# four_axis_part3.net
KiCad netlist of a schematic drawn in Altium Designer
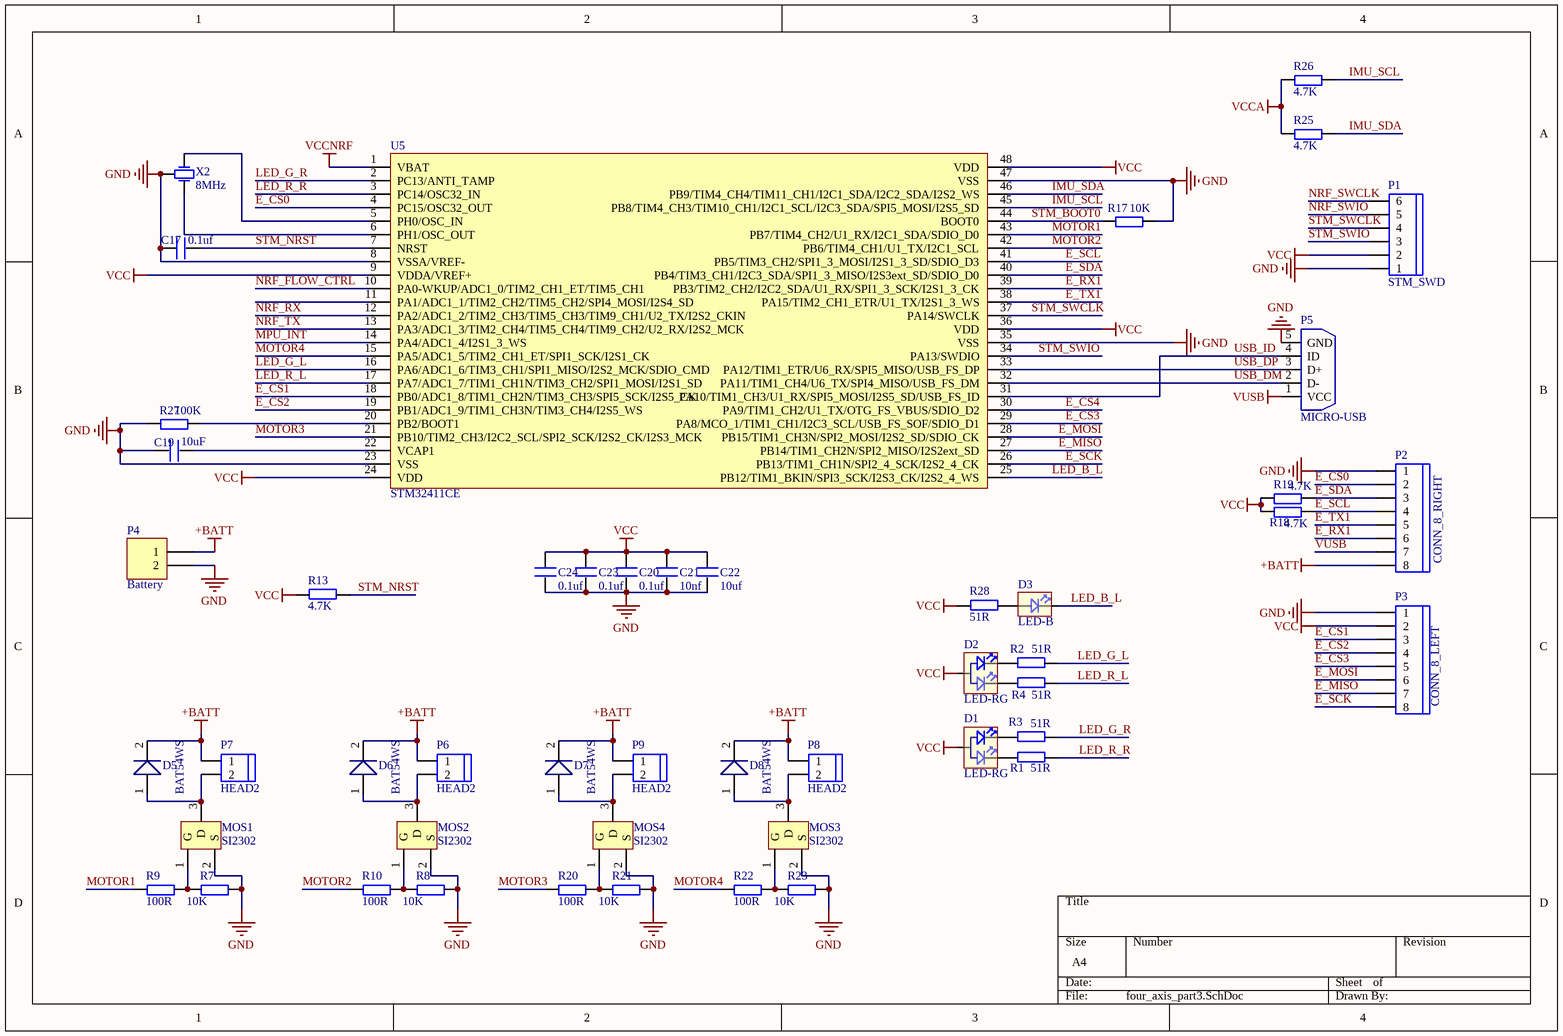
[diagram p0: four_axis_part3.SchDoc]

(export (version "E")
  (design (tool "Eeschema 10.0.6"))
  (components
    (comp (ref "C17") (value "0.1uf") (footprint "0603P") (libsource (lib "MiniFly ") (part "C")))
    (comp (ref "C19") (value "10uF") (footprint "0603P") (libsource (lib "MiniFly ") (part "C")))
    (comp (ref "C20") (value "0.1uf") (footprint "0603P") (libsource (lib "MiniFly ") (part "C")))
    (comp (ref "C21") (value "10nf") (footprint "0603P") (libsource (lib "MiniFly ") (part "C")))
    (comp (ref "C22") (value "10uf") (footprint "0603P") (libsource (lib "MiniFly ") (part "C")))
    (comp (ref "C23") (value "0.1uf") (footprint "0603P") (libsource (lib "MiniFly ") (part "C")))
    (comp (ref "C24") (value "0.1uf") (footprint "0603P") (libsource (lib "MiniFly ") (part "C")))
    (comp (ref "D1")
      (value "LED-RG")
      (footprint "LED1206  侧贴")
      (description "LED 1206 侧贴 双色")
      (libsource (lib "MiniFly ") (part "LED 1206 侧贴 双色"))
    )
    (comp (ref "D2")
      (value "LED-RG")
      (footprint "LED1206  侧贴")
      (description "LED 1206 侧贴 双色")
      (libsource (lib "MiniFly ") (part "LED 1206 侧贴 双色"))
    )
    (comp (ref "D3")
      (value "LED-B")
      (footprint "LED1206  侧贴")
      (description "LED 1206 侧贴  单色")
      (libsource (lib "MiniFly ") (part "LED 1206 侧贴  单色"))
    )
    (comp (ref "D5")
      (value "BAT54WS")
      (footprint "SOD-323")
      (description "单肖特基二极管")
      (libsource (lib "MiniFly ") (part "BAT54"))
    )
    (comp (ref "D6")
      (value "BAT54WS")
      (footprint "SOD-323")
      (description "单肖特基二极管")
      (libsource (lib "MiniFly ") (part "BAT54"))
    )
    (comp (ref "D7")
      (value "BAT54WS")
      (footprint "SOD-323")
      (description "单肖特基二极管")
      (libsource (lib "MiniFly ") (part "BAT54"))
    )
    (comp (ref "D8")
      (value "BAT54WS")
      (footprint "SOD-323")
      (description "单肖特基二极管")
      (libsource (lib "MiniFly ") (part "BAT54"))
    )
    (comp (ref "MOS1")
      (value "SI2302")
      (footprint "SO-G3/C2.5")
      (description "AP2306")
      (libsource (lib "MiniFly ") (part "MOS-N"))
    )
    (comp (ref "MOS2")
      (value "SI2302")
      (footprint "SO-G3/C2.5")
      (description "AP2306")
      (libsource (lib "MiniFly ") (part "MOS-N"))
    )
    (comp (ref "MOS3")
      (value "SI2302")
      (footprint "SO-G3/C2.5")
      (description "AP2306")
      (libsource (lib "MiniFly ") (part "MOS-N"))
    )
    (comp (ref "MOS4")
      (value "SI2302")
      (footprint "SO-G3/C2.5")
      (description "AP2306")
      (libsource (lib "MiniFly ") (part "MOS-N"))
    )
    (comp (ref "P1") (value "STM_SWD") (footprint "SH1.0-6P") (libsource (lib "MiniFly ") (part "HEAD6")))
    (comp (ref "P2")
      (value "CONN_8_RIGHT")
      (footprint "HEADER8-2.0MM")
      (libsource (lib "MiniFly ") (part "HEAD8"))
    )
    (comp (ref "P3")
      (value "CONN_8_LEFT")
      (footprint "HEADER8-2.0MM")
      (libsource (lib "MiniFly ") (part "HEAD8"))
    )
    (comp (ref "P4")
      (value "Battery")
      (footprint "HDR1X2")
      (description "Header, 2-Pin")
      (fields (field (name "PUBLISHER") "Altium Limited"))
      (libsource (lib "MiniFly ") (part "Header 2"))
    )
    (comp (ref "P5")
      (value "MICRO-USB")
      (footprint "MICRO_USB5P_SOP")
      (libsource (lib "MiniFly ") (part "USB5"))
    )
    (comp (ref "P6") (value "HEAD2") (footprint "HEADER2-1.25MM") (libsource (lib "MiniFly ") (part "HEAD2")))
    (comp (ref "P7") (value "HEAD2") (footprint "HEADER2-1.25MM") (libsource (lib "MiniFly ") (part "HEAD2")))
    (comp (ref "P8") (value "HEAD2") (footprint "HEADER2-1.25MM") (libsource (lib "MiniFly ") (part "HEAD2")))
    (comp (ref "P9") (value "HEAD2") (footprint "HEADER2-1.25MM") (libsource (lib "MiniFly ") (part "HEAD2")))
    (comp (ref "R1") (value "51R") (footprint "0402") (libsource (lib "MiniFly ") (part "R")))
    (comp (ref "R2") (value "51R") (footprint "0402") (libsource (lib "MiniFly ") (part "R")))
    (comp (ref "R3") (value "51R") (footprint "0402") (libsource (lib "MiniFly ") (part "R")))
    (comp (ref "R4") (value "51R") (footprint "0402") (libsource (lib "MiniFly ") (part "R")))
    (comp (ref "R7") (value "10K") (footprint "0402") (libsource (lib "MiniFly ") (part "R")))
    (comp (ref "R8") (value "10K") (footprint "0402") (libsource (lib "MiniFly ") (part "R")))
    (comp (ref "R9") (value "100R") (footprint "0402") (libsource (lib "MiniFly ") (part "R")))
    (comp (ref "R10") (value "100R") (footprint "0402") (libsource (lib "MiniFly ") (part "R")))
    (comp (ref "R13") (value "4.7K") (footprint "0402") (libsource (lib "MiniFly ") (part "R")))
    (comp (ref "R17") (value "10K") (footprint "0402") (libsource (lib "MiniFly ") (part "R")))
    (comp (ref "R18") (value "4.7K") (footprint "0402") (libsource (lib "MiniFly ") (part "R")))
    (comp (ref "R19") (value "4.7K") (footprint "0402") (libsource (lib "MiniFly ") (part "R")))
    (comp (ref "R20") (value "100R") (footprint "0402") (libsource (lib "MiniFly ") (part "R")))
    (comp (ref "R21") (value "10K") (footprint "0402") (libsource (lib "MiniFly ") (part "R")))
    (comp (ref "R22") (value "100R") (footprint "0402") (libsource (lib "MiniFly ") (part "R")))
    (comp (ref "R23") (value "10K") (footprint "0402") (libsource (lib "MiniFly ") (part "R")))
    (comp (ref "R25") (value "4.7K") (footprint "0402") (libsource (lib "MiniFly ") (part "R")))
    (comp (ref "R26") (value "4.7K") (footprint "0402") (libsource (lib "MiniFly ") (part "R")))
    (comp (ref "R27") (value "100K") (footprint "0402") (libsource (lib "MiniFly ") (part "R")))
    (comp (ref "R28") (value "51R") (footprint "0402") (libsource (lib "MiniFly ") (part "R")))
    (comp (ref "U5")
      (value "STM32411CE")
      (footprint "UFQFPN48")
      (description "STM32411xC_xE")
      (libsource (lib "MiniFly ") (part "STM32F411xC_xE"))
    )
    (comp (ref "X2") (value "8MHz") (footprint "XTAL3215") (libsource (lib "MiniFly ") (part "XTAL-3215")))
  )
  (nets
    (net (code "1") (name "+BATT") (class "Default")
      (node (ref "D5") (pin "2") (pinfunction "2_2") (pintype "passive"))
      (node (ref "D6") (pin "2") (pinfunction "2_2") (pintype "passive"))
      (node (ref "D7") (pin "2") (pinfunction "2_2") (pintype "passive"))
      (node (ref "D8") (pin "2") (pinfunction "2_2") (pintype "passive"))
      (node (ref "P2") (pin "8") (pinfunction "8_8") (pintype "passive"))
      (node (ref "P4") (pin "1") (pinfunction "1_1") (pintype "passive"))
      (node (ref "P6") (pin "1") (pinfunction "1_1") (pintype "passive"))
      (node (ref "P7") (pin "1") (pinfunction "1_1") (pintype "passive"))
      (node (ref "P8") (pin "1") (pinfunction "1_1") (pintype "passive"))
      (node (ref "P9") (pin "1") (pinfunction "1_1") (pintype "passive"))
    )
    (net (code "2") (name "/E_CS0") (class "Default")
      (node (ref "P2") (pin "2") (pinfunction "2_2") (pintype "passive"))
      (node (ref "U5") (pin "4") (pinfunction "PC15/OSC32_OUT_4") (pintype "passive"))
    )
    (net (code "3") (name "/E_CS1") (class "Default")
      (node (ref "P3") (pin "3") (pinfunction "3_3") (pintype "passive"))
      (node (ref "U5") (pin "18") (pinfunction "PB0/ADC1_8/TIM1_CH2N/TIM3_CH3/SPI5_SCK/I2S5_CK_18") (pintype "passive"))
    )
    (net (code "4") (name "/E_CS2") (class "Default")
      (node (ref "P3") (pin "4") (pinfunction "4_4") (pintype "passive"))
      (node (ref "U5") (pin "19") (pinfunction "PB1/ADC1_9/TIM1_CH3N/TIM3_CH4/I2S5_WS_19") (pintype "passive"))
    )
    (net (code "5") (name "/E_CS3") (class "Default")
      (node (ref "P3") (pin "5") (pinfunction "5_5") (pintype "passive"))
      (node (ref "U5") (pin "29") (pinfunction "PA8/MCO_1/TIM1_CH1/I2C3_SCL/USB_FS_SOF/SDIO_D1_29") (pintype "passive"))
    )
    (net (code "6") (name "/E_CS4") (class "Default")
      (node (ref "U5") (pin "30") (pinfunction "PA9/TIM1_CH2/U1_TX/OTG_FS_VBUS/SDIO_D2_30") (pintype "passive"))
    )
    (net (code "7") (name "/E_MISO") (class "Default")
      (node (ref "P3") (pin "7") (pinfunction "7_7") (pintype "passive"))
      (node (ref "U5") (pin "27") (pinfunction "PB14/TIM1_CH2N/SPI2_MISO/I2S2ext_SD_27") (pintype "passive"))
    )
    (net (code "8") (name "/E_MOSI") (class "Default")
      (node (ref "P3") (pin "6") (pinfunction "6_6") (pintype "passive"))
      (node (ref "U5") (pin "28") (pinfunction "PB15/TIM1_CH3N/SPI2_MOSI/I2S2_SD/SDIO_CK_28") (pintype "passive"))
    )
    (net (code "9") (name "/E_RX1") (class "Default")
      (node (ref "P2") (pin "6") (pinfunction "6_6") (pintype "passive"))
      (node (ref "U5") (pin "39") (pinfunction "PB3/TIM2_CH2/I2C2_SDA/U1_RX/SPI1_3_SCK/I2S1_3_CK_39") (pintype "passive"))
    )
    (net (code "10") (name "/E_SCK") (class "Default")
      (node (ref "P3") (pin "8") (pinfunction "8_8") (pintype "passive"))
      (node (ref "U5") (pin "26") (pinfunction "PB13/TIM1_CH1N/SPI2_4_SCK/I2S2_4_CK_26") (pintype "passive"))
    )
    (net (code "11") (name "/E_SCL") (class "Default")
      (node (ref "P2") (pin "4") (pinfunction "4_4") (pintype "passive"))
      (node (ref "R18") (pin "2") (pintype "passive"))
      (node (ref "U5") (pin "41") (pinfunction "PB5/TIM3_CH2/SPI1_3_MOSI/I2S1_3_SD/SDIO_D3_41") (pintype "passive"))
    )
    (net (code "12") (name "/E_SDA") (class "Default")
      (node (ref "P2") (pin "3") (pinfunction "3_3") (pintype "passive"))
      (node (ref "R19") (pin "2") (pintype "passive"))
      (node (ref "U5") (pin "40") (pinfunction "PB4/TIM3_CH1/I2C3_SDA/SPI1_3_MISO/I2S3ext_SD/SDIO_D0_40") (pintype "passive"))
    )
    (net (code "13") (name "/E_TX1") (class "Default")
      (node (ref "P2") (pin "5") (pinfunction "5_5") (pintype "passive"))
      (node (ref "U5") (pin "38") (pinfunction "PA15/TIM2_CH1_ETR/U1_TX/I2S1_3_WS_38") (pintype "passive"))
    )
    (net (code "14") (name "/IMU_SCL") (class "Default")
      (node (ref "R26") (pin "2") (pintype "passive"))
      (node (ref "U5") (pin "45") (pinfunction "PB8/TIM4_CH3/TIM10_CH1/I2C1_SCL/I2C3_SDA/SPI5_MOSI/I2S5_SD_45") (pintype "passive"))
    )
    (net (code "15") (name "/IMU_SDA") (class "Default")
      (node (ref "R25") (pin "2") (pintype "passive"))
      (node (ref "U5") (pin "46") (pinfunction "PB9/TIM4_CH4/TIM11_CH1/I2C1_SDA/I2C2_SDA/I2S2_WS_46") (pintype "passive"))
    )
    (net (code "16") (name "/LED_B_L") (class "Default")
      (node (ref "D3") (pin "1") (pinfunction "1_1") (pintype "passive"))
      (node (ref "U5") (pin "25") (pinfunction "PB12/TIM1_BKIN/SPI3_SCK/I2S3_CK/I2S2_4_WS_25") (pintype "passive"))
    )
    (net (code "17") (name "/LED_G_L") (class "Default")
      (node (ref "R2") (pin "1") (pintype "passive"))
      (node (ref "U5") (pin "16") (pinfunction "PA6/ADC1_6/TIM3_CH1/SPI1_MISO/I2S2_MCK/SDIO_CMD_16") (pintype "passive"))
    )
    (net (code "18") (name "/LED_G_R") (class "Default")
      (node (ref "R3") (pin "1") (pintype "passive"))
      (node (ref "U5") (pin "2") (pinfunction "PC13/ANTI_TAMP_2") (pintype "passive"))
    )
    (net (code "19") (name "/LED_R_L") (class "Default")
      (node (ref "R4") (pin "1") (pintype "passive"))
      (node (ref "U5") (pin "17") (pinfunction "PA7/ADC1_7/TIM1_CH1N/TIM3_CH2/SPI1_MOSI/I2S1_SD_17") (pintype "passive"))
    )
    (net (code "20") (name "/LED_R_R") (class "Default")
      (node (ref "R1") (pin "1") (pintype "passive"))
      (node (ref "U5") (pin "3") (pinfunction "PC14/OSC32_IN_3") (pintype "passive"))
    )
    (net (code "21") (name "/MOTOR1") (class "Default")
      (node (ref "R9") (pin "1") (pintype "passive"))
      (node (ref "U5") (pin "43") (pinfunction "PB7/TIM4_CH2/U1_RX/I2C1_SDA/SDIO_D0_43") (pintype "passive"))
    )
    (net (code "22") (name "/MOTOR2") (class "Default")
      (node (ref "R10") (pin "1") (pintype "passive"))
      (node (ref "U5") (pin "42") (pinfunction "PB6/TIM4_CH1/U1_TX/I2C1_SCL_42") (pintype "passive"))
    )
    (net (code "23") (name "/MOTOR3") (class "Default")
      (node (ref "R20") (pin "1") (pintype "passive"))
      (node (ref "U5") (pin "21") (pinfunction "PB10/TIM2_CH3/I2C2_SCL/SPI2_SCK/I2S2_CK/I2S3_MCK_21") (pintype "passive"))
    )
    (net (code "24") (name "/MOTOR4") (class "Default")
      (node (ref "R22") (pin "1") (pintype "passive"))
      (node (ref "U5") (pin "15") (pinfunction "PA5/ADC1_5/TIM2_CH1_ET/SPI1_SCK/I2S1_CK_15") (pintype "passive"))
    )
    (net (code "25") (name "/MPU_INT") (class "Default")
      (node (ref "U5") (pin "14") (pinfunction "PA4/ADC1_4/I2S1_3_WS_14") (pintype "passive"))
    )
    (net (code "26") (name "/NRF_FLOW_CTRL") (class "Default")
      (node (ref "U5") (pin "10") (pinfunction "PA0-WKUP/ADC1_0/TIM2_CH1_ET/TIM5_CH1_10") (pintype "passive"))
    )
    (net (code "27") (name "/NRF_RX") (class "Default")
      (node (ref "U5") (pin "12") (pinfunction "PA2/ADC1_2/TIM2_CH3/TIM5_CH3/TIM9_CH1/U2_TX/I2S2_CKIN_12") (pintype "passive"))
    )
    (net (code "28") (name "/NRF_SWCLK") (class "Default")
      (node (ref "P1") (pin "6") (pinfunction "6_6") (pintype "passive"))
    )
    (net (code "29") (name "/NRF_SWIO") (class "Default")
      (node (ref "P1") (pin "5") (pinfunction "5_5") (pintype "passive"))
    )
    (net (code "30") (name "/NRF_TX") (class "Default")
      (node (ref "U5") (pin "13") (pinfunction "PA3/ADC1_3/TIM2_CH4/TIM5_CH4/TIM9_CH2/U2_RX/I2S2_MCK_13") (pintype "passive"))
    )
    (net (code "31") (name "/STM_BOOT0") (class "Default")
      (node (ref "R17") (pin "1") (pintype "passive"))
      (node (ref "U5") (pin "44") (pinfunction "BOOT0_44") (pintype "passive"))
    )
    (net (code "32") (name "/STM_NRST") (class "Default")
      (node (ref "C17") (pin "2") (pintype "passive"))
      (node (ref "R13") (pin "1") (pintype "passive"))
      (node (ref "U5") (pin "7") (pinfunction "NRST_7") (pintype "passive"))
    )
    (net (code "33") (name "/STM_SWCLK") (class "Default")
      (node (ref "P1") (pin "4") (pinfunction "4_4") (pintype "passive"))
      (node (ref "U5") (pin "37") (pinfunction "PA14/SWCLK_37") (pintype "passive"))
    )
    (net (code "34") (name "/STM_SWIO") (class "Default")
      (node (ref "P1") (pin "3") (pinfunction "3_3") (pintype "passive"))
      (node (ref "U5") (pin "34") (pinfunction "PA13/SWDIO_34") (pintype "passive"))
    )
    (net (code "35") (name "/USB_DM") (class "Default")
      (node (ref "P5") (pin "2") (pinfunction "D-_2") (pintype "passive"))
      (node (ref "U5") (pin "32") (pinfunction "PA11/TIM1_CH4/U6_TX/SPI4_MISO/USB_FS_DM_32") (pintype "passive"))
    )
    (net (code "36") (name "/USB_DP") (class "Default")
      (node (ref "P5") (pin "3") (pinfunction "D+_3") (pintype "passive"))
      (node (ref "U5") (pin "33") (pinfunction "PA12/TIM1_ETR/U6_RX/SPI5_MISO/USB_FS_DP_33") (pintype "passive"))
    )
    (net (code "37") (name "/USB_ID") (class "Default")
      (node (ref "P5") (pin "4") (pinfunction "ID_4") (pintype "passive"))
      (node (ref "U5") (pin "31") (pinfunction "PA10/TIM1_CH3/U1_RX/SPI5_MOSI/I2S5_SD/USB_FS_ID_31") (pintype "passive"))
    )
    (net (code "38") (name "GND") (class "Default")
      (node (ref "C17") (pin "1") (pintype "passive"))
      (node (ref "C19") (pin "1") (pintype "passive"))
      (node (ref "C20") (pin "1") (pintype "passive"))
      (node (ref "C21") (pin "1") (pintype "passive"))
      (node (ref "C22") (pin "1") (pintype "passive"))
      (node (ref "C23") (pin "1") (pintype "passive"))
      (node (ref "C24") (pin "1") (pintype "passive"))
      (node (ref "MOS1") (pin "2") (pinfunction "S_2") (pintype "passive"))
      (node (ref "MOS2") (pin "2") (pinfunction "S_2") (pintype "passive"))
      (node (ref "MOS3") (pin "2") (pinfunction "S_2") (pintype "passive"))
      (node (ref "MOS4") (pin "2") (pinfunction "S_2") (pintype "passive"))
      (node (ref "P1") (pin "1") (pinfunction "1_1") (pintype "passive"))
      (node (ref "P2") (pin "1") (pinfunction "1_1") (pintype "passive"))
      (node (ref "P3") (pin "1") (pinfunction "1_1") (pintype "passive"))
      (node (ref "P4") (pin "2") (pinfunction "2_2") (pintype "passive"))
      (node (ref "P5") (pin "5") (pinfunction "GND_5") (pintype "passive"))
      (node (ref "R17") (pin "2") (pintype "passive"))
      (node (ref "R21") (pin "2") (pintype "passive"))
      (node (ref "R23") (pin "2") (pintype "passive"))
      (node (ref "R27") (pin "1") (pintype "passive"))
      (node (ref "R7") (pin "2") (pintype "passive"))
      (node (ref "R8") (pin "2") (pintype "passive"))
      (node (ref "U5") (pin "23") (pinfunction "VSS_23") (pintype "passive"))
      (node (ref "U5") (pin "35") (pinfunction "VSS_35") (pintype "passive"))
      (node (ref "U5") (pin "47") (pinfunction "VSS_47") (pintype "passive"))
      (node (ref "U5") (pin "8") (pinfunction "VSSA/VREF-_8") (pintype "passive"))
      (node (ref "X2") (pin "2") (pinfunction "GND_2") (pintype "passive"))
    )
    (net (code "39") (name "Net-(D1-Pad1)") (class "Default")
      (node (ref "D1") (pin "1") (pinfunction "1_1") (pintype "passive"))
      (node (ref "R1") (pin "2") (pintype "passive"))
    )
    (net (code "40") (name "Net-(D1-Pad2)") (class "Default")
      (node (ref "D1") (pin "2") (pinfunction "2_2") (pintype "passive"))
      (node (ref "R3") (pin "2") (pintype "passive"))
    )
    (net (code "41") (name "Net-(D2-Pad1)") (class "Default")
      (node (ref "D2") (pin "1") (pinfunction "1_1") (pintype "passive"))
      (node (ref "R4") (pin "2") (pintype "passive"))
    )
    (net (code "42") (name "Net-(D2-Pad2)") (class "Default")
      (node (ref "D2") (pin "2") (pinfunction "2_2") (pintype "passive"))
      (node (ref "R2") (pin "2") (pintype "passive"))
    )
    (net (code "43") (name "Net-(D3-Pad3)") (class "Default")
      (node (ref "D3") (pin "3") (pinfunction "3_3") (pintype "passive"))
      (node (ref "R28") (pin "1") (pintype "passive"))
    )
    (net (code "44") (name "Net-(MOS1-D)") (class "Default")
      (node (ref "D5") (pin "1") (pinfunction "1_1") (pintype "passive"))
      (node (ref "MOS1") (pin "3") (pinfunction "D_3") (pintype "passive"))
      (node (ref "P7") (pin "2") (pinfunction "2_2") (pintype "passive"))
    )
    (net (code "45") (name "Net-(MOS1-G)") (class "Default")
      (node (ref "MOS1") (pin "1") (pinfunction "G_1") (pintype "passive"))
      (node (ref "R7") (pin "1") (pintype "passive"))
      (node (ref "R9") (pin "2") (pintype "passive"))
    )
    (net (code "46") (name "Net-(MOS2-D)") (class "Default")
      (node (ref "D6") (pin "1") (pinfunction "1_1") (pintype "passive"))
      (node (ref "MOS2") (pin "3") (pinfunction "D_3") (pintype "passive"))
      (node (ref "P6") (pin "2") (pinfunction "2_2") (pintype "passive"))
    )
    (net (code "47") (name "Net-(MOS2-G)") (class "Default")
      (node (ref "MOS2") (pin "1") (pinfunction "G_1") (pintype "passive"))
      (node (ref "R10") (pin "2") (pintype "passive"))
      (node (ref "R8") (pin "1") (pintype "passive"))
    )
    (net (code "48") (name "Net-(MOS3-D)") (class "Default")
      (node (ref "D8") (pin "1") (pinfunction "1_1") (pintype "passive"))
      (node (ref "MOS3") (pin "3") (pinfunction "D_3") (pintype "passive"))
      (node (ref "P8") (pin "2") (pinfunction "2_2") (pintype "passive"))
    )
    (net (code "49") (name "Net-(MOS3-G)") (class "Default")
      (node (ref "MOS3") (pin "1") (pinfunction "G_1") (pintype "passive"))
      (node (ref "R22") (pin "2") (pintype "passive"))
      (node (ref "R23") (pin "1") (pintype "passive"))
    )
    (net (code "50") (name "Net-(MOS4-D)") (class "Default")
      (node (ref "D7") (pin "1") (pinfunction "1_1") (pintype "passive"))
      (node (ref "MOS4") (pin "3") (pinfunction "D_3") (pintype "passive"))
      (node (ref "P9") (pin "2") (pinfunction "2_2") (pintype "passive"))
    )
    (net (code "51") (name "Net-(MOS4-G)") (class "Default")
      (node (ref "MOS4") (pin "1") (pinfunction "G_1") (pintype "passive"))
      (node (ref "R20") (pin "2") (pintype "passive"))
      (node (ref "R21") (pin "1") (pintype "passive"))
    )
    (net (code "52") (name "Net-(U5-PB2{slash}BOOT1)") (class "Default")
      (node (ref "R27") (pin "2") (pintype "passive"))
      (node (ref "U5") (pin "20") (pinfunction "PB2/BOOT1_20") (pintype "passive"))
    )
    (net (code "53") (name "Net-(U5-PH0{slash}OSC_IN)") (class "Default")
      (node (ref "U5") (pin "5") (pinfunction "PH0/OSC_IN_5") (pintype "passive"))
      (node (ref "X2") (pin "1") (pinfunction "OSC1_1") (pintype "passive"))
    )
    (net (code "54") (name "Net-(U5-PH1{slash}OSC_OUT)") (class "Default")
      (node (ref "U5") (pin "6") (pinfunction "PH1/OSC_OUT_6") (pintype "passive"))
      (node (ref "X2") (pin "3") (pinfunction "OSC2_3") (pintype "passive"))
    )
    (net (code "55") (name "Net-(U5-VCAP1)") (class "Default")
      (node (ref "C19") (pin "2") (pintype "passive"))
      (node (ref "U5") (pin "22") (pinfunction "VCAP1_22") (pintype "passive"))
    )
    (net (code "56") (name "VCC") (class "Default")
      (node (ref "C20") (pin "2") (pintype "passive"))
      (node (ref "C21") (pin "2") (pintype "passive"))
      (node (ref "C22") (pin "2") (pintype "passive"))
      (node (ref "C23") (pin "2") (pintype "passive"))
      (node (ref "C24") (pin "2") (pintype "passive"))
      (node (ref "D1") (pin "3") (pinfunction "3_3") (pintype "passive"))
      (node (ref "D2") (pin "3") (pinfunction "3_3") (pintype "passive"))
      (node (ref "P1") (pin "2") (pinfunction "2_2") (pintype "passive"))
      (node (ref "P3") (pin "2") (pinfunction "2_2") (pintype "passive"))
      (node (ref "R13") (pin "2") (pintype "passive"))
      (node (ref "R18") (pin "1") (pintype "passive"))
      (node (ref "R19") (pin "1") (pintype "passive"))
      (node (ref "R28") (pin "2") (pintype "passive"))
      (node (ref "U5") (pin "24") (pinfunction "VDD_24") (pintype "passive"))
      (node (ref "U5") (pin "36") (pinfunction "VDD_36") (pintype "passive"))
      (node (ref "U5") (pin "48") (pinfunction "VDD_48") (pintype "passive"))
      (node (ref "U5") (pin "9") (pinfunction "VDDA/VREF+_9") (pintype "passive"))
    )
    (net (code "57") (name "VCCA") (class "Default")
      (node (ref "R25") (pin "1") (pintype "passive"))
      (node (ref "R26") (pin "1") (pintype "passive"))
    )
    (net (code "58") (name "VCCNRF") (class "Default")
      (node (ref "U5") (pin "1") (pinfunction "VBAT_1") (pintype "passive"))
    )
    (net (code "59") (name "VUSB") (class "Default")
      (node (ref "P2") (pin "7") (pinfunction "7_7") (pintype "passive"))
      (node (ref "P5") (pin "1") (pinfunction "VCC_1") (pintype "passive"))
    )
    (net (code "60") (name "unconnected-(D3-Pad2)") (class "Default")
      (node (ref "D3") (pin "2") (pinfunction "2_2") (pintype "passive"))
    )
    (net (code "61") (name "unconnected-(U5-PA1{slash}ADC1_1{slash}TIM2_CH2{slash}TIM5_CH2{slash}SPI4_MOSI{slash}I2S4_SD-Pad11)") (class "Default")
      (node (ref "U5") (pin "11") (pinfunction "PA1/ADC1_1/TIM2_CH2/TIM5_CH2/SPI4_MOSI/I2S4_SD_11") (pintype "passive"))
    )
  )
)
